# Top_Level.net
KiCad netlist of a schematic drawn in Altium Designer
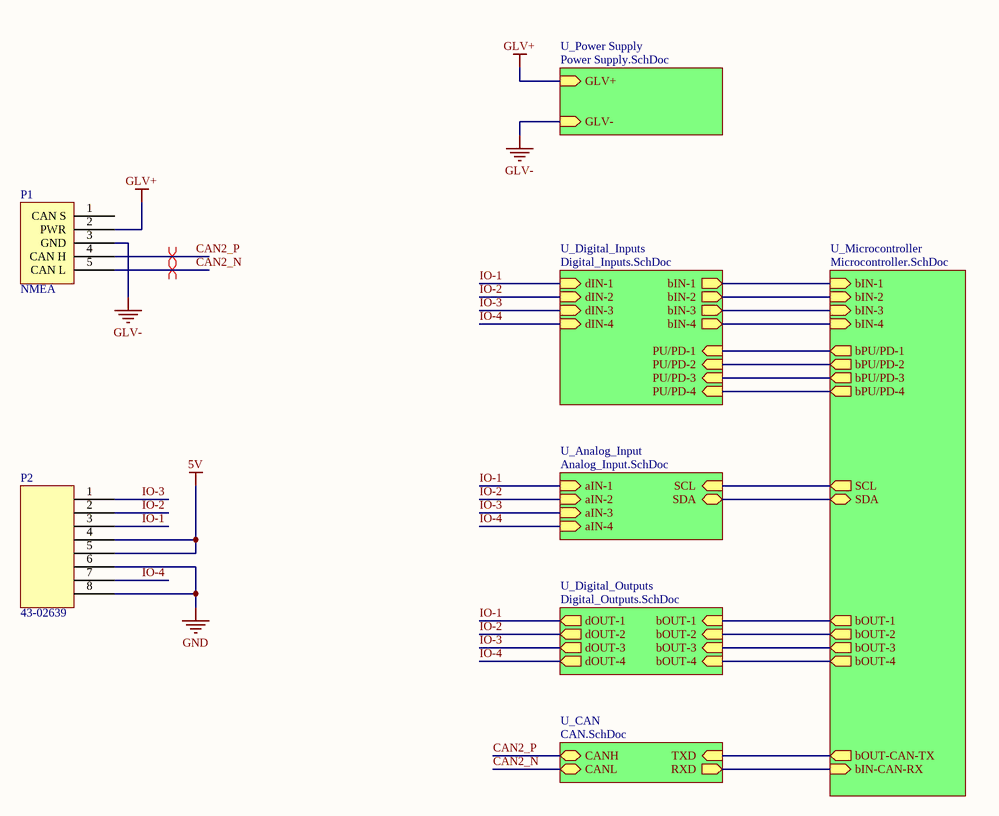
[diagram p0: Top Level.SchDoc]

(export (version "E")
  (design (tool "Eeschema 10.0.6"))
  (components
    (comp (ref "P1")
      (value "NMEA")
      (footprint "43-01203")
      (description "M12 NMEA 2000 Header")
      (fields
        (field (name "PART NUMBER") "43-01203")
        (field (name "DIGIKEY PART NUMBER") "626-1511-ND")
        (field (name "CONTACT") "Gold")
      )
      (libsource (lib "ts_standard_connectors") (part "NMEA"))
    )
    (comp (ref "P2")
      (value "43-02639")
      (footprint "43-02639")
      (description "M12, 8 Pin Connector")
      (fields (field (name "CONTACT") "Copper Alloy"))
      (libsource (lib "ts_standard_connectors") (part "43-02639"))
    )
  )
  (nets
    (net (code "1") (name "/CAN2_N") (class "Default")
      (node (ref "P1") (pin "5") (pinfunction "CAN_L_5") (pintype "passive"))
    )
    (net (code "2") (name "/CAN2_P") (class "Default")
      (node (ref "P1") (pin "4") (pinfunction "CAN_H_4") (pintype "passive"))
    )
    (net (code "3") (name "/IO-1") (class "Default")
      (node (ref "P2") (pin "3") (pinfunction "3_3") (pintype "passive"))
    )
    (net (code "4") (name "/IO-2") (class "Default")
      (node (ref "P2") (pin "2") (pinfunction "2_2") (pintype "passive"))
    )
    (net (code "5") (name "/IO-3") (class "Default")
      (node (ref "P2") (pin "1") (pinfunction "1_1") (pintype "passive"))
    )
    (net (code "6") (name "/IO-4") (class "Default")
      (node (ref "P2") (pin "7") (pinfunction "7_7") (pintype "passive"))
    )
    (net (code "23") (name "5V") (class "Default")
      (node (ref "P2") (pin "4") (pinfunction "4_4") (pintype "passive"))
      (node (ref "P2") (pin "5") (pinfunction "5_5") (pintype "passive"))
    )
    (net (code "24") (name "GLV+") (class "Default")
      (node (ref "P1") (pin "2") (pinfunction "PWR_2") (pintype "passive"))
    )
    (net (code "25") (name "GLV-") (class "Default")
      (node (ref "P1") (pin "3") (pinfunction "GND_3") (pintype "passive"))
    )
    (net (code "26") (name "GND") (class "Default")
      (node (ref "P2") (pin "6") (pinfunction "6_6") (pintype "passive"))
      (node (ref "P2") (pin "8") (pinfunction "8_8") (pintype "passive"))
    )
    (net (code "27") (name "unconnected-(P1-CAN_S-Pad1)") (class "Default")
      (node (ref "P1") (pin "1") (pinfunction "CAN_S_1") (pintype "passive"))
    )
  )
)
